# power-E01.net
KiCad netlist of a schematic drawn in EAGLE
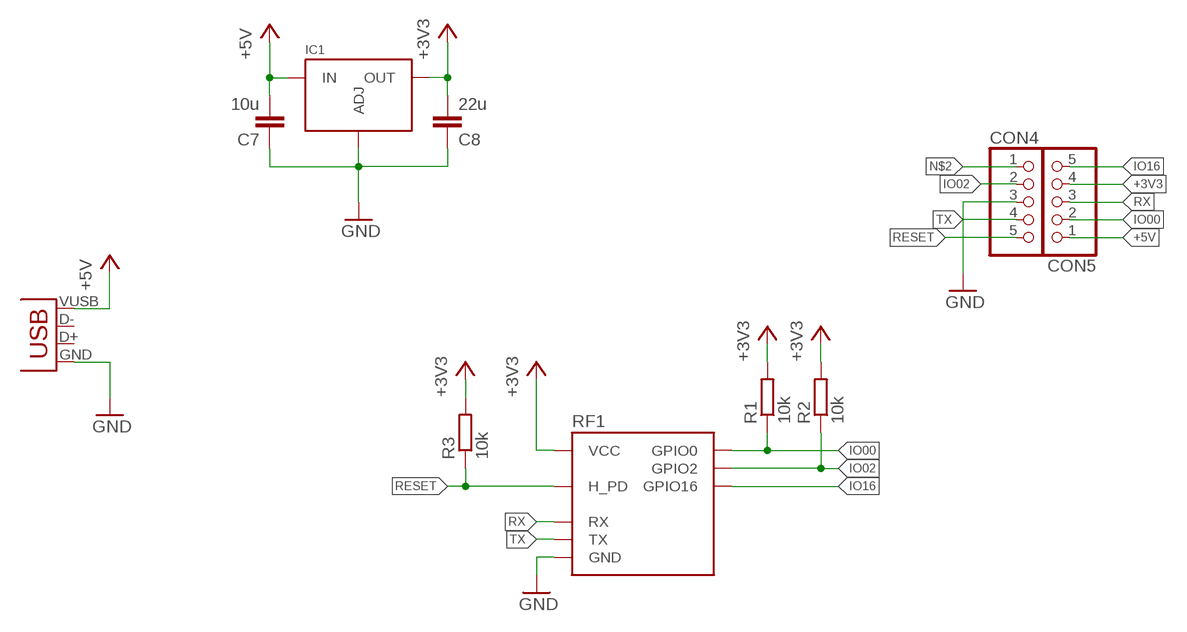
[diagram p0: schematic, sheet 1]

(export (version "E")
  (design (tool "Eeschema 10.0.6"))
  (components
    (comp (ref "C7")
      (value "10u")
      (footprint "eagle-import:C0805")
      (libsource (lib "eagle-import") (part "C-EUC0805"))
    )
    (comp (ref "C8")
      (value "22u")
      (footprint "eagle-import:C0805")
      (libsource (lib "eagle-import") (part "C-EUC0805"))
    )
    (comp (ref "CON1")
      (value "USBMICRO-NO_CENTER")
      (footprint "eagle-import:USB-MICRO-SMD-NO_CENTER")
      (libsource (lib "eagle-import") (part "USBMICRO-NO_CENTER"))
    )
    (comp (ref "CON4")
      (value "GENERIC-1X5")
      (footprint "eagle-import:PINHEADER-100MIL-1X5-NOSILK")
      (libsource (lib "eagle-import") (part "GENERIC-1X5"))
    )
    (comp (ref "CON5")
      (value "GENERIC-1X5")
      (footprint "eagle-import:PINHEADER-100MIL-1X5-NOSILK")
      (libsource (lib "eagle-import") (part "GENERIC-1X5"))
    )
    (comp (ref "IC1")
      (value "REGULATOR-LM317-SOT223")
      (footprint "eagle-import:SOT223")
      (libsource (lib "eagle-import") (part "REGULATOR-LM317-SOT223"))
    )
    (comp (ref "R1")
      (value "10k")
      (footprint "eagle-import:R0603")
      (libsource (lib "eagle-import") (part "R-EU_R0603"))
    )
    (comp (ref "R2")
      (value "10k")
      (footprint "eagle-import:R0603")
      (libsource (lib "eagle-import") (part "R-EU_R0603"))
    )
    (comp (ref "R3")
      (value "10k")
      (footprint "eagle-import:R0603")
      (libsource (lib "eagle-import") (part "R-EU_R0603"))
    )
    (comp (ref "RF1")
      (value "ESP2866-ESP-01THT-NOSILK")
      (footprint "eagle-import:ESP8266-ESP-01-NOSILK")
      (libsource (lib "eagle-import") (part "ESP2866-ESP-01THT-NOSILK"))
    )
  )
  (nets
    (net (code "1") (name "+3V3") (class "Default")
      (node (ref "C8") (pin "2") (pinfunction "2_2") (pintype "passive"))
      (node (ref "CON5") (pin "4") (pinfunction "4_4") (pintype "passive"))
      (node (ref "IC1") (pin "2") (pinfunction "OUT_2") (pintype "bidirectional"))
      (node (ref "IC1") (pin "4") (pinfunction "OUT_4") (pintype "bidirectional"))
      (node (ref "R1") (pin "2") (pinfunction "2_2") (pintype "passive"))
      (node (ref "R2") (pin "2") (pinfunction "2_2") (pintype "passive"))
      (node (ref "R3") (pin "2") (pinfunction "2_2") (pintype "passive"))
      (node (ref "RF1") (pin "VCC") (pinfunction "VCC_VCC") (pintype "bidirectional"))
    )
    (net (code "2") (name "+5V") (class "Default")
      (node (ref "C7") (pin "2") (pinfunction "2_2") (pintype "passive"))
      (node (ref "CON1") (pin "VUSB") (pinfunction "VBUS_VUSB") (pintype "bidirectional"))
      (node (ref "CON5") (pin "1") (pinfunction "1_1") (pintype "passive"))
      (node (ref "IC1") (pin "3") (pinfunction "IN_3") (pintype "bidirectional"))
    )
    (net (code "3") (name "GND") (class "Default")
      (node (ref "C7") (pin "1") (pinfunction "1_1") (pintype "passive"))
      (node (ref "C8") (pin "1") (pinfunction "1_1") (pintype "passive"))
      (node (ref "CON1") (pin "GND") (pinfunction "GND_GND") (pintype "bidirectional"))
      (node (ref "CON4") (pin "3") (pinfunction "3_3") (pintype "passive"))
      (node (ref "IC1") (pin "1") (pinfunction "ADJ_1") (pintype "bidirectional"))
      (node (ref "RF1") (pin "GND") (pinfunction "GND_GND") (pintype "bidirectional"))
    )
    (net (code "4") (name "IO00") (class "Default")
      (node (ref "CON5") (pin "2") (pinfunction "2_2") (pintype "passive"))
      (node (ref "R1") (pin "1") (pinfunction "1_1") (pintype "passive"))
      (node (ref "RF1") (pin "GPIO0") (pinfunction "GPIO0_GPIO0") (pintype "bidirectional"))
    )
    (net (code "5") (name "IO02") (class "Default")
      (node (ref "CON4") (pin "2") (pinfunction "2_2") (pintype "passive"))
      (node (ref "R2") (pin "1") (pinfunction "1_1") (pintype "passive"))
      (node (ref "RF1") (pin "GPIO2") (pinfunction "GPIO2_GPIO2") (pintype "bidirectional"))
    )
    (net (code "6") (name "IO16") (class "Default")
      (node (ref "CON5") (pin "5") (pinfunction "5_5") (pintype "passive"))
      (node (ref "RF1") (pin "GPIO16") (pinfunction "GPIO16_GPIO16") (pintype "bidirectional"))
    )
    (net (code "7") (name "N$2") (class "Default")
      (node (ref "CON4") (pin "1") (pinfunction "1_1") (pintype "passive"))
    )
    (net (code "8") (name "RESET") (class "Default")
      (node (ref "CON4") (pin "5") (pinfunction "5_5") (pintype "passive"))
      (node (ref "R3") (pin "1") (pinfunction "1_1") (pintype "passive"))
      (node (ref "RF1") (pin "H_PD") (pinfunction "H_PD_H_PD") (pintype "bidirectional"))
    )
    (net (code "9") (name "RX") (class "Default")
      (node (ref "CON5") (pin "3") (pinfunction "3_3") (pintype "passive"))
      (node (ref "RF1") (pin "RX") (pinfunction "RX_RX") (pintype "bidirectional"))
    )
    (net (code "10") (name "TX") (class "Default")
      (node (ref "CON4") (pin "4") (pinfunction "4_4") (pintype "passive"))
      (node (ref "RF1") (pin "TX") (pinfunction "TX_TX") (pintype "bidirectional"))
    )
    (net (code "11") (name "unconnected-(CON1-PadD+)") (class "Default")
      (node (ref "CON1") (pin "D+") (pinfunction "D+_D+") (pintype "bidirectional"))
    )
    (net (code "12") (name "unconnected-(CON1-PadD-)") (class "Default")
      (node (ref "CON1") (pin "D-") (pinfunction "D-_D-") (pintype "bidirectional"))
    )
  )
)
